# InputsFibras.net
KiCad netlist of a schematic drawn in Altium Designer
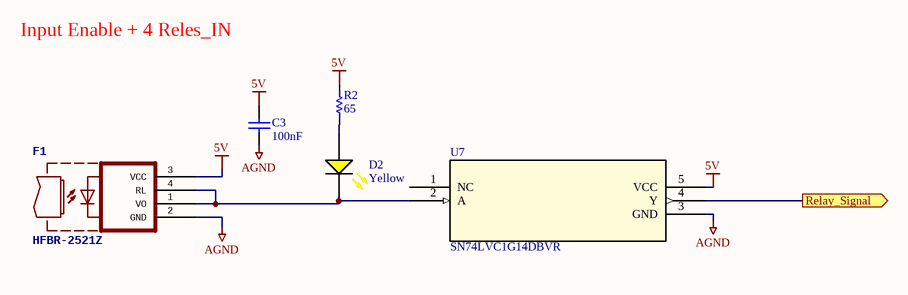
[diagram p0: InputsFibras.SchDoc]

(export (version "E")
  (design (tool "Eeschema 10.0.6"))
  (components
    (comp (ref "C3")
      (value "100nF")
      (footprint "CAP_0603")
      (description "0.1µF ±10% 50V Ceramic Capacitor X7R 0603 (1608 Metric)")
      (fields (field (name "MF") "KEMET") (field (name "CREATED") "2020_06_15_DAarancibia"))
      (libsource (lib "Schlib1") (part "Cap_0603"))
    )
    (comp (ref "D2")
      (value "Yellow")
      (footprint "LED_0603_Yellow")
      (description "Yellow 590nm LED Indication - Discrete 2V 0603 (1608 Metric)")
      (fields (field (name "MF") "Würth Elektronik") (field (name "CREATED") "2020_07_06_DAarancibia"))
      (libsource (lib "Schlib1") (part "Led_0603_Yellow"))
    )
    (comp (ref "F1")
      (value "HFBR-2521Z")
      (footprint "FO_Rx_HFBR-2521Z")
      (description "Fiber Optic Receiver  5MBd -43dBm 4.75V ~ 5.25V 10mA")
      (fields (field (name "MF") "Broadcom Limited") (field (name "CREATED") "2020_07_06_DArancibia"))
      (libsource (lib "Schlib1") (part "FO_Rx_HFBR-2521"))
    )
    (comp (ref "R2")
      (value "65")
      (footprint "RES_0805")
      (description "10 kOhms ±1% 0.125W, 1/8W Chip Resistor 0805 (2012 Metric) Automotive AEC-Q200 Thick Film")
      (fields
        (field (name "MF") "Panasonic Electronic Components")
        (field (name "CREATED") "2020_06_15_DAarancibia")
      )
      (libsource (lib "Schlib1") (part "Res_0805"))
    )
    (comp (ref "U7")
      (value "SN74LVC1G14DBVR")
      (footprint "DBV5-M")
      (description "No Description Available")
      (fields (field (name "COPYRIGHT") "Copyright (C) 2023 Ultra Librarian. All rights reserved."))
      (libsource (lib "Schlib1") (part "SN74LVC1G14DBVR"))
    )
  )
  (nets
    (net (code "1") (name "/Relay_Signal") (class "Default")
      (node (ref "U7") (pin "4") (pinfunction "Y_4") (pintype "output"))
    )
    (net (code "2") (name "5V") (class "Default")
      (node (ref "C3") (pin "1") (pinfunction "1_1") (pintype "passive"))
      (node (ref "F1") (pin "3") (pinfunction "VCC_3") (pintype "power_in"))
      (node (ref "R2") (pin "2") (pinfunction "2_2") (pintype "passive"))
      (node (ref "U7") (pin "5") (pinfunction "VCC_5") (pintype "power_in"))
    )
    (net (code "3") (name "AGND") (class "Default")
      (node (ref "C3") (pin "2") (pinfunction "2_2") (pintype "passive"))
      (node (ref "F1") (pin "2") (pinfunction "GND_2") (pintype "power_in"))
      (node (ref "U7") (pin "3") (pinfunction "GND_3") (pintype "power_in"))
    )
    (net (code "4") (name "Net-(D2-A)") (class "Default")
      (node (ref "D2") (pin "1") (pinfunction "A_1") (pintype "passive"))
      (node (ref "R2") (pin "1") (pinfunction "1_1") (pintype "passive"))
    )
    (net (code "5") (name "Net-(D2-K)") (class "Default")
      (node (ref "D2") (pin "2") (pinfunction "K_2") (pintype "passive"))
      (node (ref "F1") (pin "1") (pinfunction "VO_1") (pintype "passive"))
      (node (ref "F1") (pin "4") (pinfunction "RL_4") (pintype "passive"))
      (node (ref "U7") (pin "2") (pinfunction "A_2") (pintype "input"))
    )
    (net (code "6") (name "unconnected-(U7-NC-Pad1)") (class "Default")
      (node (ref "U7") (pin "1") (pinfunction "NC_1") (pintype "passive"))
    )
  )
)
